# svf4.net
KiCad netlist of a schematic drawn in EAGLE
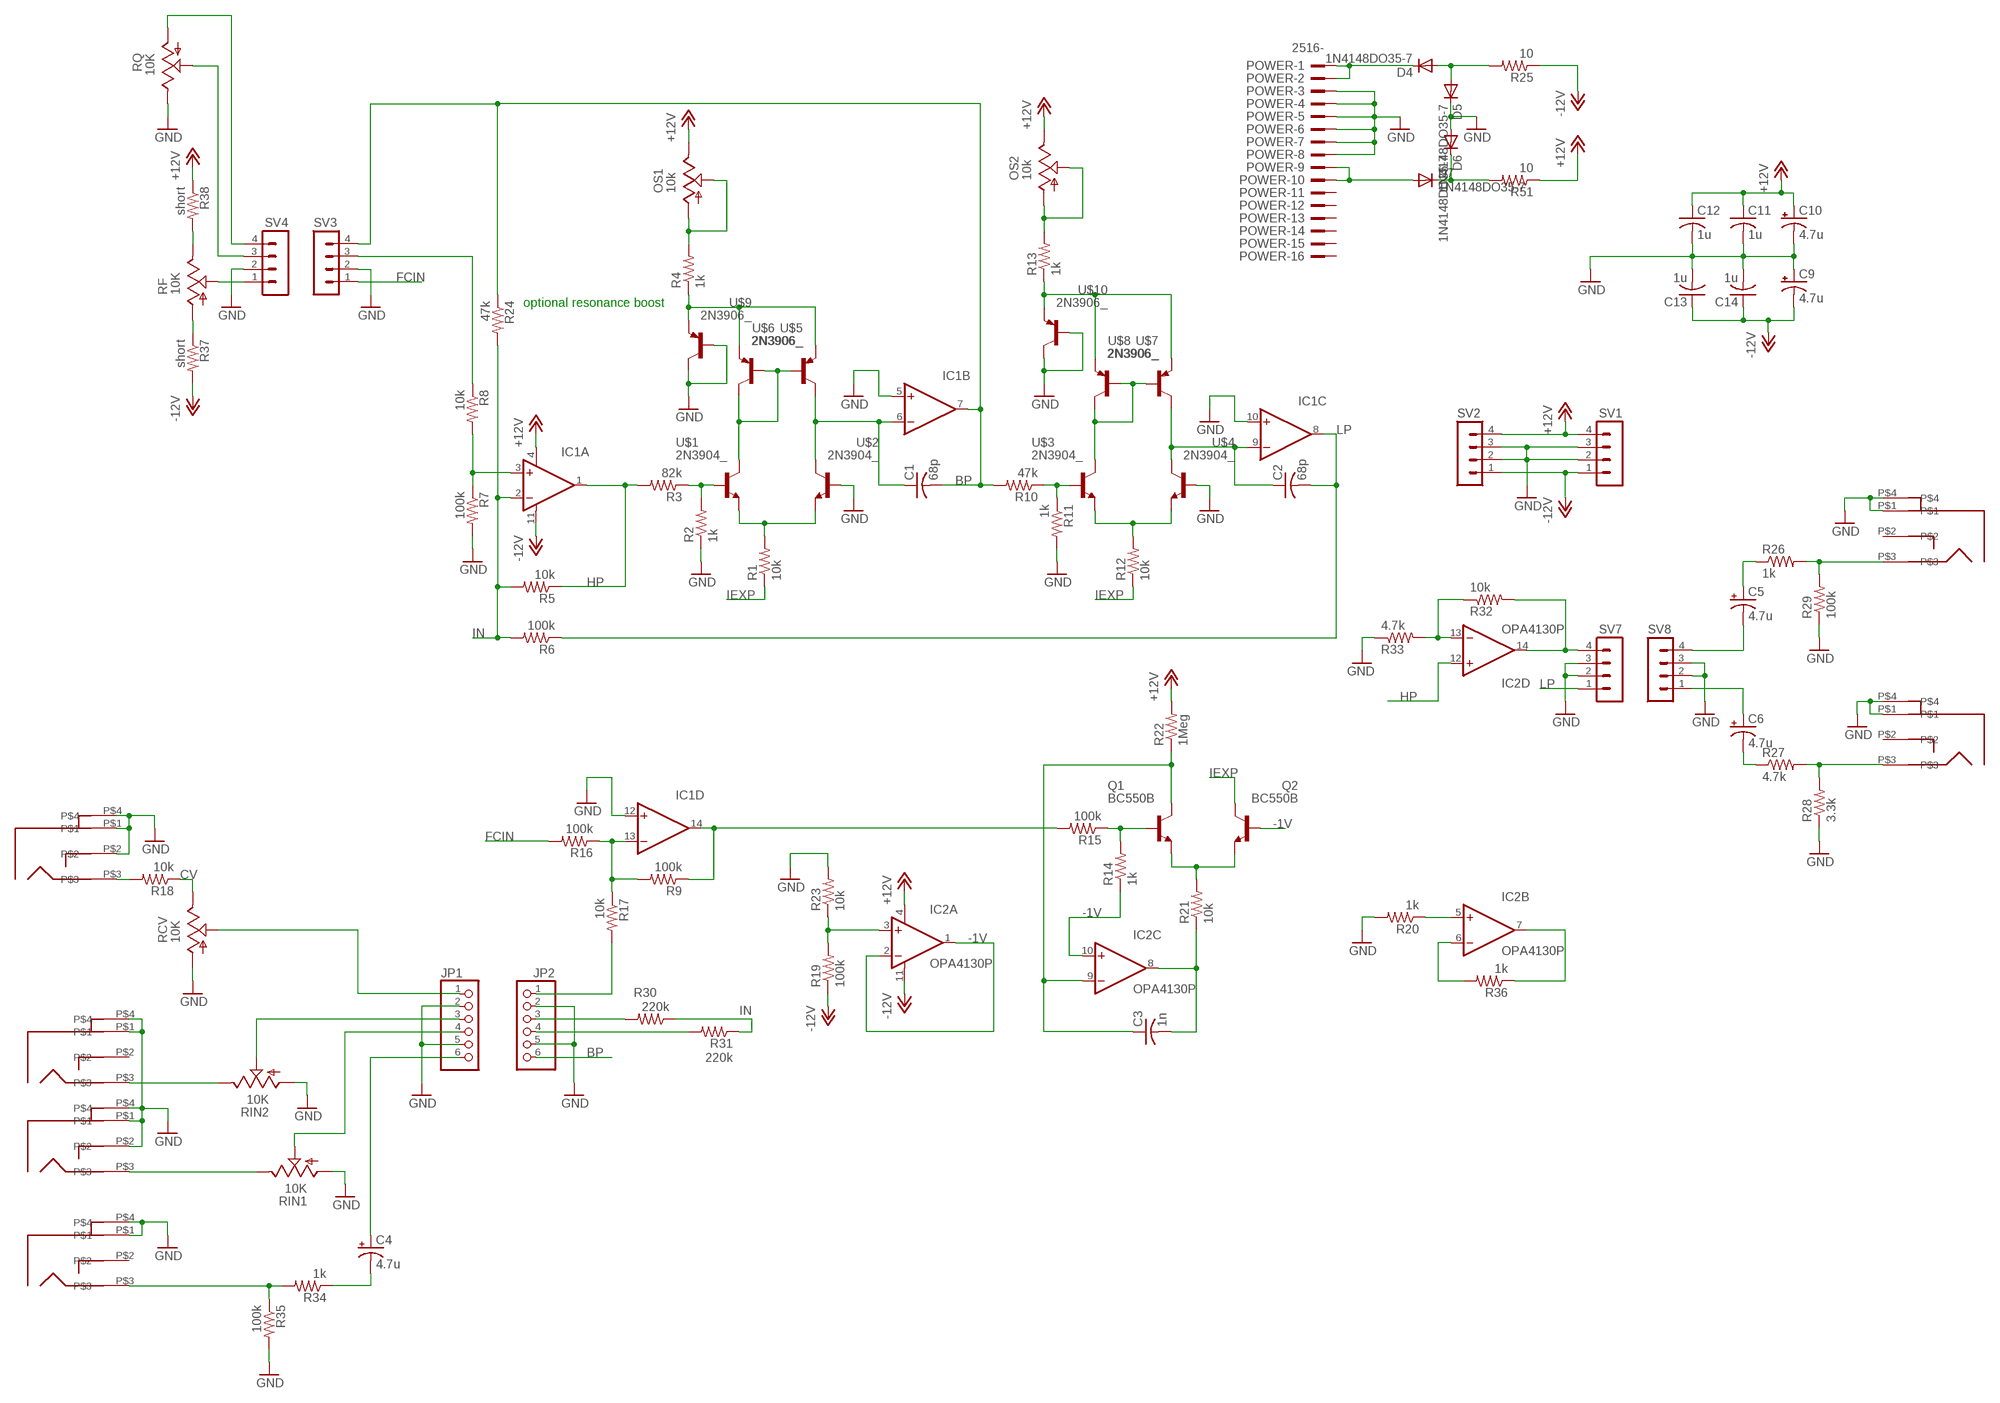
[diagram p0: schematic, sheet 1]

(export (version "E")
  (design (tool "Eeschema 10.0.6"))
  (components
    (comp (ref "BPOUT")
      (value "PJ301BM")
      (footprint "eagle-import:PJ301BM")
      (libsource (lib "eagle-import") (part "PJ301BM"))
    )
    (comp (ref "C1")
      (value "68p")
      (footprint "eagle-import:C050-025X075")
      (libsource (lib "eagle-import") (part "C-US050-025X075"))
    )
    (comp (ref "C2")
      (value "68p")
      (footprint "eagle-import:C050-025X075")
      (libsource (lib "eagle-import") (part "C-US050-025X075"))
    )
    (comp (ref "C3")
      (value "1n")
      (footprint "eagle-import:C050-025X075")
      (libsource (lib "eagle-import") (part "C-US050-025X075"))
    )
    (comp (ref "C4")
      (value "4.7u")
      (footprint "eagle-import:E2,5-6")
      (libsource (lib "eagle-import") (part "CPOL-USE2.5-6"))
    )
    (comp (ref "C5")
      (value "4.7u")
      (footprint "eagle-import:E2,5-6")
      (libsource (lib "eagle-import") (part "CPOL-USE2.5-6"))
    )
    (comp (ref "C6")
      (value "4.7u")
      (footprint "eagle-import:E2,5-6")
      (libsource (lib "eagle-import") (part "CPOL-USE2.5-6"))
    )
    (comp (ref "C9")
      (value "4.7u")
      (footprint "eagle-import:E2,5-6")
      (libsource (lib "eagle-import") (part "CPOL-USE2.5-6"))
    )
    (comp (ref "C10")
      (value "4.7u")
      (footprint "eagle-import:E2,5-6")
      (libsource (lib "eagle-import") (part "CPOL-USE2.5-6"))
    )
    (comp (ref "C11")
      (value "1u")
      (footprint "eagle-import:C050-025X075")
      (libsource (lib "eagle-import") (part "C-US050-025X075"))
    )
    (comp (ref "C12")
      (value "1u")
      (footprint "eagle-import:C050-025X075")
      (libsource (lib "eagle-import") (part "C-US050-025X075"))
    )
    (comp (ref "C13")
      (value "1u")
      (footprint "eagle-import:C050-025X075")
      (libsource (lib "eagle-import") (part "C-US050-025X075"))
    )
    (comp (ref "C14")
      (value "1u")
      (footprint "eagle-import:C050-025X075")
      (libsource (lib "eagle-import") (part "C-US050-025X075"))
    )
    (comp (ref "CVIN")
      (value "PJ301BM")
      (footprint "eagle-import:PJ301BM")
      (libsource (lib "eagle-import") (part "PJ301BM"))
    )
    (comp (ref "D4")
      (value "1N4148DO35-7")
      (footprint "eagle-import:DO35-7")
      (libsource (lib "eagle-import") (part "1N4148DO35-7"))
    )
    (comp (ref "D5")
      (value "1N4148DO35-7")
      (footprint "eagle-import:DO35-7")
      (libsource (lib "eagle-import") (part "1N4148DO35-7"))
    )
    (comp (ref "D6")
      (value "1N4148DO35-7")
      (footprint "eagle-import:DO35-7")
      (libsource (lib "eagle-import") (part "1N4148DO35-7"))
    )
    (comp (ref "D7")
      (value "1N4148DO35-7")
      (footprint "eagle-import:DO35-7")
      (libsource (lib "eagle-import") (part "1N4148DO35-7"))
    )
    (comp (ref "HPOUT")
      (value "PJ301BM")
      (footprint "eagle-import:PJ301BM")
      (libsource (lib "eagle-import") (part "PJ301BM"))
    )
    (comp (ref "IC1")
      (value "OPA4130P")
      (footprint "eagle-import:DIL14")
      (libsource (lib "eagle-import") (part "OPA4130P"))
    )
    (comp (ref "IC2")
      (value "OPA4130P")
      (footprint "eagle-import:DIL14")
      (libsource (lib "eagle-import") (part "OPA4130P"))
    )
    (comp (ref "IN")
      (value "PJ301BM")
      (footprint "eagle-import:PJ301BM")
      (libsource (lib "eagle-import") (part "PJ301BM"))
    )
    (comp (ref "IN1")
      (value "PJ301BM")
      (footprint "eagle-import:PJ301BM")
      (libsource (lib "eagle-import") (part "PJ301BM"))
    )
    (comp (ref "JP1")
      (value "PINHD-1X6")
      (footprint "eagle-import:1X06")
      (libsource (lib "eagle-import") (part "PINHD-1X6"))
    )
    (comp (ref "JP2")
      (value "PINHD-1X6")
      (footprint "eagle-import:1X06")
      (libsource (lib "eagle-import") (part "PINHD-1X6"))
    )
    (comp (ref "LPOUT")
      (value "PJ301BM")
      (footprint "eagle-import:PJ301BM")
      (libsource (lib "eagle-import") (part "PJ301BM"))
    )
    (comp (ref "OS1")
      (value "10k")
      (footprint "eagle-import:S64W")
      (libsource (lib "eagle-import") (part "TRIM_US-S64W"))
    )
    (comp (ref "OS2")
      (value "10k")
      (footprint "eagle-import:S64W")
      (libsource (lib "eagle-import") (part "TRIM_US-S64W"))
    )
    (comp (ref "POWER")
      (value "2516-")
      (footprint "eagle-import:PAK100_2500-16")
      (libsource (lib "eagle-import") (part "2516-"))
    )
    (comp (ref "Q1")
      (value "BC550B")
      (footprint "eagle-import:TO92-EBC")
      (libsource (lib "eagle-import") (part "BC550B"))
    )
    (comp (ref "Q2")
      (value "BC550B")
      (footprint "eagle-import:TO92-EBC")
      (libsource (lib "eagle-import") (part "BC550B"))
    )
    (comp (ref "R1")
      (value "10k")
      (footprint "eagle-import:0207_2V")
      (libsource (lib "eagle-import") (part "R-US_0207/2V"))
    )
    (comp (ref "R2")
      (value "1k")
      (footprint "eagle-import:0207_2V")
      (libsource (lib "eagle-import") (part "R-US_0207/2V"))
    )
    (comp (ref "R3")
      (value "82k")
      (footprint "eagle-import:0207_2V")
      (libsource (lib "eagle-import") (part "R-US_0207/2V"))
    )
    (comp (ref "R4")
      (value "1k")
      (footprint "eagle-import:0207_2V")
      (libsource (lib "eagle-import") (part "R-US_0207/2V"))
    )
    (comp (ref "R5")
      (value "10k")
      (footprint "eagle-import:0207_2V")
      (libsource (lib "eagle-import") (part "R-US_0207/2V"))
    )
    (comp (ref "R6")
      (value "100k")
      (footprint "eagle-import:0207_2V")
      (libsource (lib "eagle-import") (part "R-US_0207/2V"))
    )
    (comp (ref "R7")
      (value "100k")
      (footprint "eagle-import:0207_2V")
      (libsource (lib "eagle-import") (part "R-US_0207/2V"))
    )
    (comp (ref "R8")
      (value "10k")
      (footprint "eagle-import:0207_2V")
      (libsource (lib "eagle-import") (part "R-US_0207/2V"))
    )
    (comp (ref "R9")
      (value "100k")
      (footprint "eagle-import:0207_2V")
      (libsource (lib "eagle-import") (part "R-US_0207/2V"))
    )
    (comp (ref "R10")
      (value "47k")
      (footprint "eagle-import:0207_2V")
      (libsource (lib "eagle-import") (part "R-US_0207/2V"))
    )
    (comp (ref "R11")
      (value "1k")
      (footprint "eagle-import:0207_2V")
      (libsource (lib "eagle-import") (part "R-US_0207/2V"))
    )
    (comp (ref "R12")
      (value "10k")
      (footprint "eagle-import:0207_2V")
      (libsource (lib "eagle-import") (part "R-US_0207/2V"))
    )
    (comp (ref "R13")
      (value "1k")
      (footprint "eagle-import:0207_2V")
      (libsource (lib "eagle-import") (part "R-US_0207/2V"))
    )
    (comp (ref "R14")
      (value "1k")
      (footprint "eagle-import:0207_2V")
      (libsource (lib "eagle-import") (part "R-US_0207/2V"))
    )
    (comp (ref "R15")
      (value "100k")
      (footprint "eagle-import:0207_2V")
      (libsource (lib "eagle-import") (part "R-US_0207/2V"))
    )
    (comp (ref "R16")
      (value "100k")
      (footprint "eagle-import:0207_2V")
      (libsource (lib "eagle-import") (part "R-US_0207/2V"))
    )
    (comp (ref "R17")
      (value "10k")
      (footprint "eagle-import:0207_2V")
      (libsource (lib "eagle-import") (part "R-US_0207/2V"))
    )
    (comp (ref "R18")
      (value "10k")
      (footprint "eagle-import:0204_7")
      (libsource (lib "eagle-import") (part "R-US_0204/7"))
    )
    (comp (ref "R19")
      (value "100k")
      (footprint "eagle-import:0207_2V")
      (libsource (lib "eagle-import") (part "R-US_0207/2V"))
    )
    (comp (ref "R20")
      (value "1k")
      (footprint "eagle-import:0207_2V")
      (libsource (lib "eagle-import") (part "R-US_0207/2V"))
    )
    (comp (ref "R21")
      (value "10k")
      (footprint "eagle-import:0207_2V")
      (libsource (lib "eagle-import") (part "R-US_0207/2V"))
    )
    (comp (ref "R22")
      (value "1Meg")
      (footprint "eagle-import:0207_2V")
      (libsource (lib "eagle-import") (part "R-US_0207/2V"))
    )
    (comp (ref "R23")
      (value "10k")
      (footprint "eagle-import:0207_2V")
      (libsource (lib "eagle-import") (part "R-US_0207/2V"))
    )
    (comp (ref "R24")
      (value "47k")
      (footprint "eagle-import:0207_2V")
      (libsource (lib "eagle-import") (part "R-US_0207/2V"))
    )
    (comp (ref "R25")
      (value "10")
      (footprint "eagle-import:0207_2V")
      (libsource (lib "eagle-import") (part "R-US_0207/2V"))
    )
    (comp (ref "R26")
      (value "1k")
      (footprint "eagle-import:0204_7")
      (libsource (lib "eagle-import") (part "R-US_0204/7"))
    )
    (comp (ref "R27")
      (value "4.7k")
      (footprint "eagle-import:0204_7")
      (libsource (lib "eagle-import") (part "R-US_0204/7"))
    )
    (comp (ref "R28")
      (value "3.3k")
      (footprint "eagle-import:0204_7")
      (libsource (lib "eagle-import") (part "R-US_0204/7"))
    )
    (comp (ref "R29")
      (value "100k")
      (footprint "eagle-import:0204_7")
      (libsource (lib "eagle-import") (part "R-US_0204/7"))
    )
    (comp (ref "R30")
      (value "220k")
      (footprint "eagle-import:0207_2V")
      (libsource (lib "eagle-import") (part "R-US_0207/2V"))
    )
    (comp (ref "R31")
      (value "220k")
      (footprint "eagle-import:0207_2V")
      (libsource (lib "eagle-import") (part "R-US_0207/2V"))
    )
    (comp (ref "R32")
      (value "10k")
      (footprint "eagle-import:0207_2V")
      (libsource (lib "eagle-import") (part "R-US_0207/2V"))
    )
    (comp (ref "R33")
      (value "4.7k")
      (footprint "eagle-import:0207_2V")
      (libsource (lib "eagle-import") (part "R-US_0207/2V"))
    )
    (comp (ref "R34")
      (value "1k")
      (footprint "eagle-import:0204_7")
      (libsource (lib "eagle-import") (part "R-US_0204/7"))
    )
    (comp (ref "R35")
      (value "100k")
      (footprint "eagle-import:0204_7")
      (libsource (lib "eagle-import") (part "R-US_0204/7"))
    )
    (comp (ref "R36")
      (value "1k")
      (footprint "eagle-import:0207_2V")
      (libsource (lib "eagle-import") (part "R-US_0207/2V"))
    )
    (comp (ref "R37")
      (value "short")
      (footprint "eagle-import:0204_7")
      (libsource (lib "eagle-import") (part "R-US_0204/7"))
    )
    (comp (ref "R38")
      (value "short")
      (footprint "eagle-import:0204_7")
      (libsource (lib "eagle-import") (part "R-US_0204/7"))
    )
    (comp (ref "R51")
      (value "10")
      (footprint "eagle-import:0207_2V")
      (libsource (lib "eagle-import") (part "R-US_0207/2V"))
    )
    (comp (ref "RCV")
      (value "10K")
      (footprint "eagle-import:EVUFXJ")
      (libsource (lib "eagle-import") (part "US-EVUF3J"))
    )
    (comp (ref "RF")
      (value "10K")
      (footprint "eagle-import:EVUFXJ")
      (libsource (lib "eagle-import") (part "US-EVUF3J"))
    )
    (comp (ref "RIN1")
      (value "10K")
      (footprint "eagle-import:EVUFXJ")
      (libsource (lib "eagle-import") (part "US-EVUF3J"))
    )
    (comp (ref "RIN2")
      (value "10K")
      (footprint "eagle-import:EVUFXJ")
      (libsource (lib "eagle-import") (part "US-EVUF3J"))
    )
    (comp (ref "RQ")
      (value "10K")
      (footprint "eagle-import:EVUFXJ")
      (libsource (lib "eagle-import") (part "US-EVUF3J"))
    )
    (comp (ref "SV1")
      (value "MA04-1")
      (footprint "eagle-import:MA04-1")
      (libsource (lib "eagle-import") (part "MA04-1"))
    )
    (comp (ref "SV2")
      (value "MA04-1")
      (footprint "eagle-import:MA04-1")
      (libsource (lib "eagle-import") (part "MA04-1"))
    )
    (comp (ref "SV3")
      (value "MA04-1")
      (footprint "eagle-import:MA04-1")
      (libsource (lib "eagle-import") (part "MA04-1"))
    )
    (comp (ref "SV4")
      (value "MA04-1")
      (footprint "eagle-import:MA04-1")
      (libsource (lib "eagle-import") (part "MA04-1"))
    )
    (comp (ref "SV7")
      (value "MA04-1")
      (footprint "eagle-import:MA04-1")
      (libsource (lib "eagle-import") (part "MA04-1"))
    )
    (comp (ref "SV8")
      (value "MA04-1")
      (footprint "eagle-import:MA04-1")
      (libsource (lib "eagle-import") (part "MA04-1"))
    )
    (comp (ref "U$1")
      (value "2N3904_")
      (footprint "eagle-import:TO92-EBC")
      (libsource (lib "eagle-import") (part "2N3904_"))
    )
    (comp (ref "U$2")
      (value "2N3904_")
      (footprint "eagle-import:TO92-EBC")
      (libsource (lib "eagle-import") (part "2N3904_"))
    )
    (comp (ref "U$3")
      (value "2N3904_")
      (footprint "eagle-import:TO92-EBC")
      (libsource (lib "eagle-import") (part "2N3904_"))
    )
    (comp (ref "U$4")
      (value "2N3904_")
      (footprint "eagle-import:TO92-EBC")
      (libsource (lib "eagle-import") (part "2N3904_"))
    )
    (comp (ref "U$5")
      (value "2N3906_")
      (footprint "eagle-import:TO92-EBC")
      (libsource (lib "eagle-import") (part "2N3906_"))
    )
    (comp (ref "U$6")
      (value "2N3906_")
      (footprint "eagle-import:TO92-EBC")
      (libsource (lib "eagle-import") (part "2N3906_"))
    )
    (comp (ref "U$7")
      (value "2N3906_")
      (footprint "eagle-import:TO92-EBC")
      (libsource (lib "eagle-import") (part "2N3906_"))
    )
    (comp (ref "U$8")
      (value "2N3906_")
      (footprint "eagle-import:TO92-EBC")
      (libsource (lib "eagle-import") (part "2N3906_"))
    )
    (comp (ref "U$9")
      (value "2N3906_")
      (footprint "eagle-import:TO92-EBC")
      (libsource (lib "eagle-import") (part "2N3906_"))
    )
    (comp (ref "U$10")
      (value "2N3906_")
      (footprint "eagle-import:TO92-EBC")
      (libsource (lib "eagle-import") (part "2N3906_"))
    )
  )
  (nets
    (net (code "1") (name "+12V") (class "Default")
      (node (ref "C10") (pin "+") (pinfunction "+_+") (pintype "passive"))
      (node (ref "C11") (pin "1") (pinfunction "1_1") (pintype "passive"))
      (node (ref "C12") (pin "1") (pinfunction "1_1") (pintype "passive"))
      (node (ref "IC1") (pin "4") (pinfunction "V+_4") (pintype "power_in"))
      (node (ref "IC2") (pin "4") (pinfunction "V+_4") (pintype "power_in"))
      (node (ref "OS1") (pin "E") (pinfunction "E_E") (pintype "passive"))
      (node (ref "OS2") (pin "E") (pinfunction "E_E") (pintype "passive"))
      (node (ref "R22") (pin "2") (pinfunction "2_2") (pintype "passive"))
      (node (ref "R38") (pin "1") (pinfunction "1_1") (pintype "passive"))
      (node (ref "R51") (pin "1") (pinfunction "1_1") (pintype "passive"))
      (node (ref "SV1") (pin "4") (pinfunction "4_4") (pintype "passive"))
      (node (ref "SV2") (pin "4") (pinfunction "4_4") (pintype "passive"))
    )
    (net (code "2") (name "-12V") (class "Default")
      (node (ref "C13") (pin "1") (pinfunction "1_1") (pintype "passive"))
      (node (ref "C14") (pin "1") (pinfunction "1_1") (pintype "passive"))
      (node (ref "C9") (pin "-") (pinfunction "-_-") (pintype "passive"))
      (node (ref "IC1") (pin "11") (pinfunction "V-_11") (pintype "power_in"))
      (node (ref "IC2") (pin "11") (pinfunction "V-_11") (pintype "power_in"))
      (node (ref "R19") (pin "1") (pinfunction "1_1") (pintype "passive"))
      (node (ref "R25") (pin "1") (pinfunction "1_1") (pintype "passive"))
      (node (ref "R37") (pin "2") (pinfunction "2_2") (pintype "passive"))
      (node (ref "SV1") (pin "1") (pinfunction "1_1") (pintype "passive"))
      (node (ref "SV2") (pin "1") (pinfunction "1_1") (pintype "passive"))
    )
    (net (code "3") (name "/-1V") (class "Default")
      (node (ref "IC2") (pin "1") (pinfunction "OUT_1") (pintype "output"))
      (node (ref "IC2") (pin "10") (pinfunction "+IN_10") (pintype "input"))
      (node (ref "IC2") (pin "2") (pinfunction "-IN_2") (pintype "input"))
      (node (ref "Q2") (pin "B") (pinfunction "B_B") (pintype "passive"))
      (node (ref "R14") (pin "1") (pinfunction "1_1") (pintype "passive"))
    )
    (net (code "4") (name "/BP") (class "Default")
      (node (ref "C1") (pin "2") (pinfunction "2_2") (pintype "passive"))
      (node (ref "IC1") (pin "7") (pinfunction "OUT_7") (pintype "output"))
      (node (ref "JP2") (pin "6") (pinfunction "6_6") (pintype "passive"))
      (node (ref "R10") (pin "2") (pinfunction "2_2") (pintype "passive"))
      (node (ref "R24") (pin "1") (pinfunction "1_1") (pintype "passive"))
      (node (ref "SV3") (pin "4") (pinfunction "4_4") (pintype "passive"))
    )
    (net (code "5") (name "/CV") (class "Default")
      (node (ref "R18") (pin "1") (pinfunction "1_1") (pintype "passive"))
      (node (ref "RCV") (pin "3") (pinfunction "E_3") (pintype "passive"))
    )
    (net (code "6") (name "/FCIN") (class "Default")
      (node (ref "R16") (pin "2") (pinfunction "2_2") (pintype "passive"))
      (node (ref "SV3") (pin "1") (pinfunction "1_1") (pintype "passive"))
    )
    (net (code "7") (name "/HP") (class "Default")
      (node (ref "IC1") (pin "1") (pinfunction "OUT_1") (pintype "output"))
      (node (ref "IC2") (pin "12") (pinfunction "+IN_12") (pintype "input"))
      (node (ref "R3") (pin "2") (pinfunction "2_2") (pintype "passive"))
      (node (ref "R5") (pin "1") (pinfunction "1_1") (pintype "passive"))
    )
    (net (code "8") (name "/IEXP") (class "Default")
      (node (ref "Q2") (pin "C") (pinfunction "C_C") (pintype "passive"))
      (node (ref "R1") (pin "1") (pinfunction "1_1") (pintype "passive"))
      (node (ref "R12") (pin "1") (pinfunction "1_1") (pintype "passive"))
    )
    (net (code "9") (name "/IN") (class "Default")
      (node (ref "IC1") (pin "2") (pinfunction "-IN_2") (pintype "input"))
      (node (ref "R24") (pin "2") (pinfunction "2_2") (pintype "passive"))
      (node (ref "R30") (pin "1") (pinfunction "1_1") (pintype "passive"))
      (node (ref "R31") (pin "1") (pinfunction "1_1") (pintype "passive"))
      (node (ref "R5") (pin "2") (pinfunction "2_2") (pintype "passive"))
      (node (ref "R6") (pin "2") (pinfunction "2_2") (pintype "passive"))
    )
    (net (code "10") (name "/LP") (class "Default")
      (node (ref "C2") (pin "2") (pinfunction "2_2") (pintype "passive"))
      (node (ref "IC1") (pin "8") (pinfunction "OUT_8") (pintype "output"))
      (node (ref "R6") (pin "1") (pinfunction "1_1") (pintype "passive"))
      (node (ref "SV7") (pin "1") (pinfunction "1_1") (pintype "passive"))
    )
    (net (code "11") (name "GND") (class "Default")
      (node (ref "BPOUT") (pin "P$1") (pinfunction "P$1_P$1") (pintype "bidirectional"))
      (node (ref "BPOUT") (pin "P$4") (pinfunction "P$4_P$4") (pintype "bidirectional"))
      (node (ref "C10") (pin "-") (pinfunction "-_-") (pintype "passive"))
      (node (ref "C11") (pin "2") (pinfunction "2_2") (pintype "passive"))
      (node (ref "C12") (pin "2") (pinfunction "2_2") (pintype "passive"))
      (node (ref "C13") (pin "2") (pinfunction "2_2") (pintype "passive"))
      (node (ref "C14") (pin "2") (pinfunction "2_2") (pintype "passive"))
      (node (ref "C9") (pin "+") (pinfunction "+_+") (pintype "passive"))
      (node (ref "CVIN") (pin "P$1") (pinfunction "P$1_P$1") (pintype "bidirectional"))
      (node (ref "CVIN") (pin "P$2") (pinfunction "P$2_P$2") (pintype "bidirectional"))
      (node (ref "CVIN") (pin "P$4") (pinfunction "P$4_P$4") (pintype "bidirectional"))
      (node (ref "D5") (pin "C") (pinfunction "C_C") (pintype "passive"))
      (node (ref "D6") (pin "A") (pinfunction "A_A") (pintype "passive"))
      (node (ref "HPOUT") (pin "P$1") (pinfunction "P$1_P$1") (pintype "bidirectional"))
      (node (ref "HPOUT") (pin "P$4") (pinfunction "P$4_P$4") (pintype "bidirectional"))
      (node (ref "IC1") (pin "10") (pinfunction "+IN_10") (pintype "input"))
      (node (ref "IC1") (pin "12") (pinfunction "+IN_12") (pintype "input"))
      (node (ref "IC1") (pin "5") (pinfunction "+IN_5") (pintype "input"))
      (node (ref "IN") (pin "P$1") (pinfunction "P$1_P$1") (pintype "bidirectional"))
      (node (ref "IN") (pin "P$2") (pinfunction "P$2_P$2") (pintype "bidirectional"))
      (node (ref "IN") (pin "P$4") (pinfunction "P$4_P$4") (pintype "bidirectional"))
      (node (ref "IN1") (pin "P$1") (pinfunction "P$1_P$1") (pintype "bidirectional"))
      (node (ref "IN1") (pin "P$4") (pinfunction "P$4_P$4") (pintype "bidirectional"))
      (node (ref "JP1") (pin "2") (pinfunction "2_2") (pintype "passive"))
      (node (ref "JP1") (pin "5") (pinfunction "5_5") (pintype "passive"))
      (node (ref "JP2") (pin "2") (pinfunction "2_2") (pintype "passive"))
      (node (ref "JP2") (pin "5") (pinfunction "5_5") (pintype "passive"))
      (node (ref "LPOUT") (pin "P$1") (pinfunction "P$1_P$1") (pintype "bidirectional"))
      (node (ref "LPOUT") (pin "P$4") (pinfunction "P$4_P$4") (pintype "bidirectional"))
      (node (ref "POWER") (pin "3") (pinfunction "KL_3") (pintype "passive"))
      (node (ref "POWER") (pin "4") (pinfunction "KL_4") (pintype "passive"))
      (node (ref "POWER") (pin "5") (pinfunction "KL_5") (pintype "passive"))
      (node (ref "POWER") (pin "6") (pinfunction "KL_6") (pintype "passive"))
      (node (ref "POWER") (pin "7") (pinfunction "KL_7") (pintype "passive"))
      (node (ref "POWER") (pin "8") (pinfunction "KL_8") (pintype "passive"))
      (node (ref "R11") (pin "2") (pinfunction "2_2") (pintype "passive"))
      (node (ref "R2") (pin "1") (pinfunction "1_1") (pintype "passive"))
      (node (ref "R20") (pin "2") (pinfunction "2_2") (pintype "passive"))
      (node (ref "R23") (pin "2") (pinfunction "2_2") (pintype "passive"))
      (node (ref "R28") (pin "1") (pinfunction "1_1") (pintype "passive"))
      (node (ref "R29") (pin "1") (pinfunction "1_1") (pintype "passive"))
      (node (ref "R33") (pin "1") (pinfunction "1_1") (pintype "passive"))
      (node (ref "R35") (pin "2") (pinfunction "2_2") (pintype "passive"))
      (node (ref "R7") (pin "2") (pinfunction "2_2") (pintype "passive"))
      (node (ref "RCV") (pin "1") (pinfunction "A_1") (pintype "passive"))
      (node (ref "RIN1") (pin "1") (pinfunction "A_1") (pintype "passive"))
      (node (ref "RIN2") (pin "1") (pinfunction "A_1") (pintype "passive"))
      (node (ref "RQ") (pin "3") (pinfunction "E_3") (pintype "passive"))
      (node (ref "SV1") (pin "2") (pinfunction "2_2") (pintype "passive"))
      (node (ref "SV1") (pin "3") (pinfunction "3_3") (pintype "passive"))
      (node (ref "SV2") (pin "2") (pinfunction "2_2") (pintype "passive"))
      (node (ref "SV2") (pin "3") (pinfunction "3_3") (pintype "passive"))
      (node (ref "SV3") (pin "2") (pinfunction "2_2") (pintype "passive"))
      (node (ref "SV4") (pin "2") (pinfunction "2_2") (pintype "passive"))
      (node (ref "SV7") (pin "2") (pinfunction "2_2") (pintype "passive"))
      (node (ref "SV7") (pin "3") (pinfunction "3_3") (pintype "passive"))
      (node (ref "SV8") (pin "2") (pinfunction "2_2") (pintype "passive"))
      (node (ref "SV8") (pin "3") (pinfunction "3_3") (pintype "passive"))
      (node (ref "U$10") (pin "B") (pinfunction "B_B") (pintype "passive"))
      (node (ref "U$10") (pin "E") (pinfunction "C_E") (pintype "passive"))
      (node (ref "U$2") (pin "B") (pinfunction "B_B") (pintype "passive"))
      (node (ref "U$4") (pin "B") (pinfunction "B_B") (pintype "passive"))
      (node (ref "U$9") (pin "B") (pinfunction "B_B") (pintype "passive"))
      (node (ref "U$9") (pin "E") (pinfunction "C_E") (pintype "passive"))
    )
    (net (code "12") (name "Net-(BPOUT-PadP$3)") (class "Default")
      (node (ref "BPOUT") (pin "P$3") (pinfunction "P$3_P$3") (pintype "bidirectional"))
      (node (ref "R34") (pin "2") (pinfunction "2_2") (pintype "passive"))
      (node (ref "R35") (pin "1") (pinfunction "1_1") (pintype "passive"))
    )
    (net (code "13") (name "Net-(C4-Pad+)") (class "Default")
      (node (ref "C4") (pin "+") (pinfunction "+_+") (pintype "passive"))
      (node (ref "JP1") (pin "6") (pinfunction "6_6") (pintype "passive"))
    )
    (net (code "14") (name "Net-(C4-Pad-)") (class "Default")
      (node (ref "C4") (pin "-") (pinfunction "-_-") (pintype "passive"))
      (node (ref "R34") (pin "1") (pinfunction "1_1") (pintype "passive"))
    )
    (net (code "15") (name "Net-(C5-Pad+)") (class "Default")
      (node (ref "C5") (pin "+") (pinfunction "+_+") (pintype "passive"))
      (node (ref "R26") (pin "1") (pinfunction "1_1") (pintype "passive"))
    )
    (net (code "16") (name "Net-(C5-Pad-)") (class "Default")
      (node (ref "C5") (pin "-") (pinfunction "-_-") (pintype "passive"))
      (node (ref "SV8") (pin "4") (pinfunction "4_4") (pintype "passive"))
    )
    (net (code "17") (name "Net-(C6-Pad+)") (class "Default")
      (node (ref "C6") (pin "+") (pinfunction "+_+") (pintype "passive"))
      (node (ref "SV8") (pin "1") (pinfunction "1_1") (pintype "passive"))
    )
    (net (code "18") (name "Net-(C6-Pad-)") (class "Default")
      (node (ref "C6") (pin "-") (pinfunction "-_-") (pintype "passive"))
      (node (ref "R27") (pin "1") (pinfunction "1_1") (pintype "passive"))
    )
    (net (code "19") (name "Net-(CVIN-PadP$3)") (class "Default")
      (node (ref "CVIN") (pin "P$3") (pinfunction "P$3_P$3") (pintype "bidirectional"))
      (node (ref "R18") (pin "2") (pinfunction "2_2") (pintype "passive"))
    )
    (net (code "20") (name "Net-(D4-PadA)") (class "Default")
      (node (ref "D4") (pin "A") (pinfunction "A_A") (pintype "passive"))
      (node (ref "D5") (pin "A") (pinfunction "A_A") (pintype "passive"))
      (node (ref "R25") (pin "2") (pinfunction "2_2") (pintype "passive"))
    )
    (net (code "21") (name "Net-(D6-PadC)") (class "Default")
      (node (ref "D6") (pin "C") (pinfunction "C_C") (pintype "passive"))
      (node (ref "D7") (pin "C") (pinfunction "C_C") (pintype "passive"))
      (node (ref "R51") (pin "2") (pinfunction "2_2") (pintype "passive"))
    )
    (net (code "22") (name "Net-(HPOUT-PadP$3)") (class "Default")
      (node (ref "HPOUT") (pin "P$3") (pinfunction "P$3_P$3") (pintype "bidirectional"))
      (node (ref "R26") (pin "2") (pinfunction "2_2") (pintype "passive"))
      (node (ref "R29") (pin "2") (pinfunction "2_2") (pintype "passive"))
    )
    (net (code "23") (name "Net-(IC1A-+IN)") (class "Default")
      (node (ref "IC1") (pin "3") (pinfunction "+IN_3") (pintype "input"))
      (node (ref "R7") (pin "1") (pinfunction "1_1") (pintype "passive"))
      (node (ref "R8") (pin "2") (pinfunction "2_2") (pintype "passive"))
    )
    (net (code "24") (name "Net-(IC1B--IN)") (class "Default")
      (node (ref "C1") (pin "1") (pinfunction "1_1") (pintype "passive"))
      (node (ref "IC1") (pin "6") (pinfunction "-IN_6") (pintype "input"))
      (node (ref "U$2") (pin "E") (pinfunction "C_E") (pintype "passive"))
      (node (ref "U$6") (pin "E") (pinfunction "C_E") (pintype "passive"))
    )
    (net (code "25") (name "Net-(IC1C--IN)") (class "Default")
      (node (ref "C2") (pin "1") (pinfunction "1_1") (pintype "passive"))
      (node (ref "IC1") (pin "9") (pinfunction "-IN_9") (pintype "input"))
      (node (ref "U$4") (pin "E") (pinfunction "C_E") (pintype "passive"))
      (node (ref "U$8") (pin "E") (pinfunction "C_E") (pintype "passive"))
    )
    (net (code "26") (name "Net-(IC1D--IN)") (class "Default")
      (node (ref "IC1") (pin "13") (pinfunction "-IN_13") (pintype "input"))
      (node (ref "R16") (pin "1") (pinfunction "1_1") (pintype "passive"))
      (node (ref "R17") (pin "1") (pinfunction "1_1") (pintype "passive"))
      (node (ref "R9") (pin "2") (pinfunction "2_2") (pintype "passive"))
    )
    (net (code "27") (name "Net-(IC1D-OUT)") (class "Default")
      (node (ref "IC1") (pin "14") (pinfunction "OUT_14") (pintype "output"))
      (node (ref "R15") (pin "2") (pinfunction "2_2") (pintype "passive"))
      (node (ref "R9") (pin "1") (pinfunction "1_1") (pintype "passive"))
    )
    (net (code "28") (name "Net-(IC2A-+IN)") (class "Default")
      (node (ref "IC2") (pin "3") (pinfunction "+IN_3") (pintype "input"))
      (node (ref "R19") (pin "2") (pinfunction "2_2") (pintype "passive"))
      (node (ref "R23") (pin "1") (pinfunction "1_1") (pintype "passive"))
    )
    (net (code "29") (name "Net-(IC2B-+IN)") (class "Default")
      (node (ref "IC2") (pin "5") (pinfunction "+IN_5") (pintype "input"))
      (node (ref "R20") (pin "1") (pinfunction "1_1") (pintype "passive"))
    )
    (net (code "30") (name "Net-(IC2B--IN)") (class "Default")
      (node (ref "IC2") (pin "6") (pinfunction "-IN_6") (pintype "input"))
      (node (ref "R36") (pin "2") (pinfunction "2_2") (pintype "passive"))
    )
    (net (code "31") (name "Net-(IC2B-OUT)") (class "Default")
      (node (ref "IC2") (pin "7") (pinfunction "OUT_7") (pintype "output"))
      (node (ref "R36") (pin "1") (pinfunction "1_1") (pintype "passive"))
    )
    (net (code "32") (name "Net-(IC2C--IN)") (class "Default")
      (node (ref "C3") (pin "1") (pinfunction "1_1") (pintype "passive"))
      (node (ref "IC2") (pin "9") (pinfunction "-IN_9") (pintype "input"))
      (node (ref "Q1") (pin "C") (pinfunction "C_C") (pintype "passive"))
      (node (ref "R22") (pin "1") (pinfunction "1_1") (pintype "passive"))
    )
    (net (code "33") (name "Net-(IC2C-OUT)") (class "Default")
      (node (ref "C3") (pin "2") (pinfunction "2_2") (pintype "passive"))
      (node (ref "IC2") (pin "8") (pinfunction "OUT_8") (pintype "output"))
      (node (ref "R21") (pin "1") (pinfunction "1_1") (pintype "passive"))
    )
    (net (code "34") (name "Net-(IC2D--IN)") (class "Default")
      (node (ref "IC2") (pin "13") (pinfunction "-IN_13") (pintype "input"))
      (node (ref "R32") (pin "1") (pinfunction "1_1") (pintype "passive"))
      (node (ref "R33") (pin "2") (pinfunction "2_2") (pintype "passive"))
    )
    (net (code "35") (name "Net-(IC2D-OUT)") (class "Default")
      (node (ref "IC2") (pin "14") (pinfunction "OUT_14") (pintype "output"))
      (node (ref "R32") (pin "2") (pinfunction "2_2") (pintype "passive"))
      (node (ref "SV7") (pin "4") (pinfunction "4_4") (pintype "passive"))
    )
    (net (code "36") (name "Net-(JP2-Pad1)") (class "Default")
      (node (ref "JP2") (pin "1") (pinfunction "1_1") (pintype "passive"))
      (node (ref "R17") (pin "2") (pinfunction "2_2") (pintype "passive"))
    )
    (net (code "37") (name "Net-(JP2-Pad3)") (class "Default")
      (node (ref "JP2") (pin "3") (pinfunction "3_3") (pintype "passive"))
      (node (ref "R30") (pin "2") (pinfunction "2_2") (pintype "passive"))
    )
    (net (code "38") (name "Net-(JP2-Pad4)") (class "Default")
      (node (ref "JP2") (pin "4") (pinfunction "4_4") (pintype "passive"))
      (node (ref "R31") (pin "2") (pinfunction "2_2") (pintype "passive"))
    )
    (net (code "39") (name "Net-(LPOUT-PadP$3)") (class "Default")
      (node (ref "LPOUT") (pin "P$3") (pinfunction "P$3_P$3") (pintype "bidirectional"))
      (node (ref "R27") (pin "2") (pinfunction "2_2") (pintype "passive"))
      (node (ref "R28") (pin "2") (pinfunction "2_2") (pintype "passive"))
    )
    (net (code "40") (name "Net-(OS1-PadA)") (class "Default")
      (node (ref "OS1") (pin "A") (pinfunction "A_A") (pintype "passive"))
      (node (ref "OS1") (pin "S") (pinfunction "S_S") (pintype "passive"))
      (node (ref "R4") (pin "2") (pinfunction "2_2") (pintype "passive"))
    )
    (net (code "41") (name "Net-(OS2-PadA)") (class "Default")
      (node (ref "OS2") (pin "A") (pinfunction "A_A") (pintype "passive"))
      (node (ref "OS2") (pin "S") (pinfunction "S_S") (pintype "passive"))
      (node (ref "R13") (pin "2") (pinfunction "2_2") (pintype "passive"))
    )
    (net (code "42") (name "Net-(POWERA-KL)") (class "Default")
      (node (ref "D4") (pin "C") (pinfunction "C_C") (pintype "passive"))
      (node (ref "POWER") (pin "1") (pinfunction "KL_1") (pintype "passive"))
      (node (ref "POWER") (pin "2") (pinfunction "KL_2") (pintype "passive"))
    )
    (net (code "43") (name "Net-(POWERB-KL)") (class "Default")
      (node (ref "D7") (pin "A") (pinfunction "A_A") (pintype "passive"))
      (node (ref "POWER") (pin "10") (pinfunction "KL_10") (pintype "passive"))
      (node (ref "POWER") (pin "9") (pinfunction "KL_9") (pintype "passive"))
    )
    (net (code "44") (name "Net-(Q1-PadB)") (class "Default")
      (node (ref "Q1") (pin "B") (pinfunction "B_B") (pintype "passive"))
      (node (ref "R14") (pin "2") (pinfunction "2_2") (pintype "passive"))
      (node (ref "R15") (pin "1") (pinfunction "1_1") (pintype "passive"))
    )
    (net (code "45") (name "Net-(Q1-PadE)") (class "Default")
      (node (ref "Q1") (pin "E") (pinfunction "E_E") (pintype "passive"))
      (node (ref "Q2") (pin "E") (pinfunction "E_E") (pintype "passive"))
      (node (ref "R21") (pin "2") (pinfunction "2_2") (pintype "passive"))
    )
    (net (code "46") (name "Net-(R2-Pad2)") (class "Default")
      (node (ref "R2") (pin "2") (pinfunction "2_2") (pintype "passive"))
      (node (ref "R3") (pin "1") (pinfunction "1_1") (pintype "passive"))
      (node (ref "U$1") (pin "B") (pinfunction "B_B") (pintype "passive"))
    )
    (net (code "47") (name "Net-(R8-Pad1)") (class "Default")
      (node (ref "R8") (pin "1") (pinfunction "1_1") (pintype "passive"))
      (node (ref "SV3") (pin "3") (pinfunction "3_3") (pintype "passive"))
    )
    (net (code "48") (name "Net-(R10-Pad1)") (class "Default")
      (node (ref "R10") (pin "1") (pinfunction "1_1") (pintype "passive"))
      (node (ref "R11") (pin "1") (pinfunction "1_1") (pintype "passive"))
      (node (ref "U$3") (pin "B") (pinfunction "B_B") (pintype "passive"))
    )
    (net (code "49") (name "Net-(RCV-S)") (class "Default")
      (node (ref "JP1") (pin "1") (pinfunction "1_1") (pintype "passive"))
      (node (ref "RCV") (pin "2") (pinfunction "S_2") (pintype "passive"))
    )
    (net (code "50") (name "Net-(RF-A)") (class "Default")
      (node (ref "R37") (pin "1") (pinfunction "1_1") (pintype "passive"))
      (node (ref "RF") (pin "1") (pinfunction "A_1") (pintype "passive"))
    )
    (net (code "51") (name "Net-(RF-E)") (class "Default")
      (node (ref "R38") (pin "2") (pinfunction "2_2") (pintype "passive"))
      (node (ref "RF") (pin "3") (pinfunction "E_3") (pintype "passive"))
    )
    (net (code "52") (name "Net-(RF-S)") (class "Default")
      (node (ref "RF") (pin "2") (pinfunction "S_2") (pintype "passive"))
      (node (ref "SV4") (pin "1") (pinfunction "1_1") (pintype "passive"))
    )
    (net (code "53") (name "Net-(RIN1-E)") (class "Default")
      (node (ref "IN") (pin "P$3") (pinfunction "P$3_P$3") (pintype "bidirectional"))
      (node (ref "RIN1") (pin "3") (pinfunction "E_3") (pintype "passive"))
    )
    (net (code "54") (name "Net-(RIN1-S)") (class "Default")
      (node (ref "JP1") (pin "4") (pinfunction "4_4") (pintype "passive"))
      (node (ref "RIN1") (pin "2") (pinfunction "S_2") (pintype "passive"))
    )
    (net (code "55") (name "Net-(RIN2-E)") (class "Default")
      (node (ref "IN1") (pin "P$3") (pinfunction "P$3_P$3") (pintype "bidirectional"))
      (node (ref "RIN2") (pin "3") (pinfunction "E_3") (pintype "passive"))
    )
    (net (code "56") (name "Net-(RIN2-S)") (class "Default")
      (node (ref "JP1") (pin "3") (pinfunction "3_3") (pintype "passive"))
      (node (ref "RIN2") (pin "2") (pinfunction "S_2") (pintype "passive"))
    )
    (net (code "57") (name "Net-(RQ-A)") (class "Default")
      (node (ref "RQ") (pin "1") (pinfunction "A_1") (pintype "passive"))
      (node (ref "SV4") (pin "4") (pinfunction "4_4") (pintype "passive"))
    )
    (net (code "58") (name "Net-(RQ-S)") (class "Default")
      (node (ref "RQ") (pin "2") (pinfunction "S_2") (pintype "passive"))
      (node (ref "SV4") (pin "3") (pinfunction "3_3") (pintype "passive"))
    )
    (net (code "59") (name "Net-(U$1-C)") (class "Default")
      (node (ref "U$1") (pin "E") (pinfunction "C_E") (pintype "passive"))
      (node (ref "U$5") (pin "B") (pinfunction "B_B") (pintype "passive"))
      (node (ref "U$5") (pin "E") (pinfunction "C_E") (pintype "passive"))
      (node (ref "U$6") (pin "B") (pinfunction "B_B") (pintype "passive"))
    )
    (net (code "60") (name "Net-(U$1-E)") (class "Default")
      (node (ref "R1") (pin "2") (pinfunction "2_2") (pintype "passive"))
      (node (ref "U$1") (pin "C") (pinfunction "E_C") (pintype "passive"))
      (node (ref "U$2") (pin "C") (pinfunction "E_C") (pintype "passive"))
    )
    (net (code "61") (name "Net-(U$3-C)") (class "Default")
      (node (ref "U$3") (pin "E") (pinfunction "C_E") (pintype "passive"))
      (node (ref "U$7") (pin "B") (pinfunction "B_B") (pintype "passive"))
      (node (ref "U$7") (pin "E") (pinfunction "C_E") (pintype "passive"))
      (node (ref "U$8") (pin "B") (pinfunction "B_B") (pintype "passive"))
    )
    (net (code "62") (name "Net-(U$3-E)") (class "Default")
      (node (ref "R12") (pin "2") (pinfunction "2_2") (pintype "passive"))
      (node (ref "U$3") (pin "C") (pinfunction "E_C") (pintype "passive"))
      (node (ref "U$4") (pin "C") (pinfunction "E_C") (pintype "passive"))
    )
    (net (code "63") (name "Net-(U$5-E)") (class "Default")
      (node (ref "R4") (pin "1") (pinfunction "1_1") (pintype "passive"))
      (node (ref "U$5") (pin "C") (pinfunction "E_C") (pintype "passive"))
      (node (ref "U$6") (pin "C") (pinfunction "E_C") (pintype "passive"))
      (node (ref "U$9") (pin "C") (pinfunction "E_C") (pintype "passive"))
    )
    (net (code "64") (name "Net-(U$10-E)") (class "Default")
      (node (ref "R13") (pin "1") (pinfunction "1_1") (pintype "passive"))
      (node (ref "U$10") (pin "C") (pinfunction "E_C") (pintype "passive"))
      (node (ref "U$7") (pin "C") (pinfunction "E_C") (pintype "passive"))
      (node (ref "U$8") (pin "C") (pinfunction "E_C") (pintype "passive"))
    )
    (net (code "65") (name "unconnected-(BPOUT-PadP$2)") (class "Default")
      (node (ref "BPOUT") (pin "P$2") (pinfunction "P$2_P$2") (pintype "bidirectional"))
    )
    (net (code "66") (name "unconnected-(HPOUT-PadP$2)") (class "Default")
      (node (ref "HPOUT") (pin "P$2") (pinfunction "P$2_P$2") (pintype "bidirectional"))
    )
    (net (code "67") (name "unconnected-(IN1-PadP$2)") (class "Default")
      (node (ref "IN1") (pin "P$2") (pinfunction "P$2_P$2") (pintype "bidirectional"))
    )
    (net (code "68") (name "unconnected-(LPOUT-PadP$2)") (class "Default")
      (node (ref "LPOUT") (pin "P$2") (pinfunction "P$2_P$2") (pintype "bidirectional"))
    )
    (net (code "69") (name "unconnected-(POWERC-KL-Pad11)") (class "Default")
      (node (ref "POWER") (pin "11") (pinfunction "KL_11") (pintype "passive"))
    )
    (net (code "70") (name "unconnected-(POWERD-KL-Pad12)") (class "Default")
      (node (ref "POWER") (pin "12") (pinfunction "KL_12") (pintype "passive"))
    )
    (net (code "71") (name "unconnected-(POWERE-KL-Pad13)") (class "Default")
      (node (ref "POWER") (pin "13") (pinfunction "KL_13") (pintype "passive"))
    )
    (net (code "72") (name "unconnected-(POWERF-KL-Pad14)") (class "Default")
      (node (ref "POWER") (pin "14") (pinfunction "KL_14") (pintype "passive"))
    )
    (net (code "73") (name "unconnected-(POWERG-KL-Pad15)") (class "Default")
      (node (ref "POWER") (pin "15") (pinfunction "KL_15") (pintype "passive"))
    )
    (net (code "74") (name "unconnected-(POWERH-KL-Pad16)") (class "Default")
      (node (ref "POWER") (pin "16") (pinfunction "KL_16") (pintype "passive"))
    )
  )
)
